# Soprano2G-010.net
KiCad netlist of a schematic drawn in EAGLE
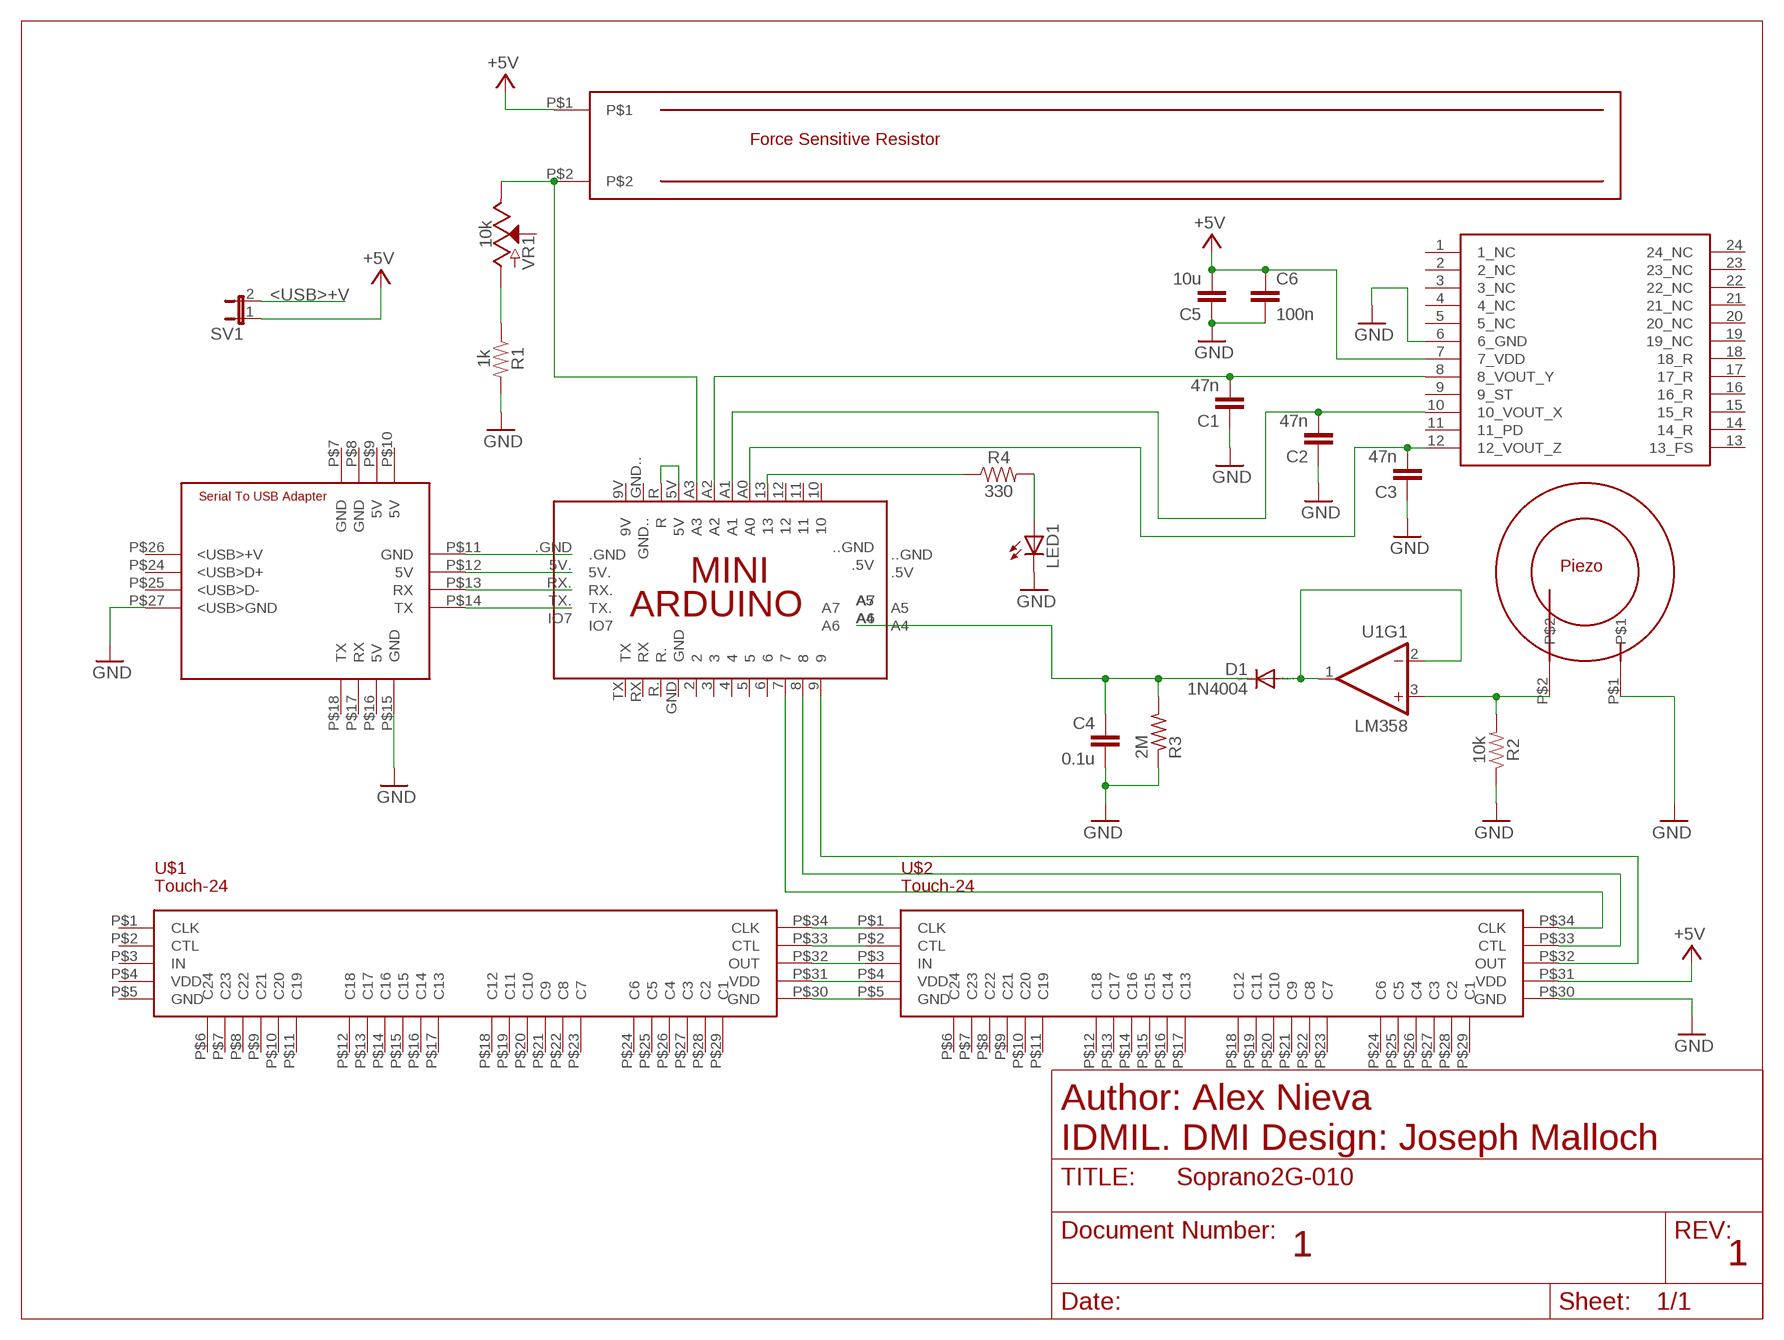
[diagram p0: schematic, sheet 1]

(export (version "E")
  (design (tool "Eeschema 10.0.6"))
  (components
    (comp (ref "C1")
      (value "47n")
      (footprint "eagle-import:C5B5.5")
      (libsource (lib "eagle-import") (part "C5/5.5"))
    )
    (comp (ref "C2")
      (value "47n")
      (footprint "eagle-import:C5B5.5")
      (libsource (lib "eagle-import") (part "C5/5.5"))
    )
    (comp (ref "C3")
      (value "47n")
      (footprint "eagle-import:C5B5.5")
      (libsource (lib "eagle-import") (part "C5/5.5"))
    )
    (comp (ref "C4")
      (value "0.1u")
      (footprint "eagle-import:C5B5.5")
      (libsource (lib "eagle-import") (part "C5/5.5"))
    )
    (comp (ref "C5")
      (value "10u")
      (footprint "eagle-import:C5B5.5")
      (libsource (lib "eagle-import") (part "C5/5.5"))
    )
    (comp (ref "C6")
      (value "100n")
      (footprint "eagle-import:C5B5.5")
      (libsource (lib "eagle-import") (part "C5/5.5"))
    )
    (comp (ref "D1")
      (value "1N4004")
      (footprint "eagle-import:DO41-10")
      (libsource (lib "eagle-import") (part "1N4004"))
    )
    (comp (ref "LED1")
      (value "LED3MM")
      (footprint "eagle-import:LED3MM")
      (libsource (lib "eagle-import") (part "LED3MM"))
    )
    (comp (ref "PCB1")
      (value "ARDUINO_MINI")
      (footprint "eagle-import:ARDUINO_MINI")
      (libsource (lib "eagle-import") (part "ARDUINO_MINI"))
    )
    (comp (ref "R1")
      (value "1k")
      (footprint "eagle-import:AXIAL-0.3")
      (libsource (lib "eagle-import") (part "1KOHM-HORIZ-1/4W-1%"))
    )
    (comp (ref "R2")
      (value "10k")
      (footprint "eagle-import:AXIAL-0.3")
      (libsource (lib "eagle-import") (part "10KOHM-HORIZ-1/4W-1%"))
    )
    (comp (ref "R3")
      (value "2M")
      (footprint "eagle-import:0204_7")
      (libsource (lib "eagle-import") (part "R-US_0204/7"))
    )
    (comp (ref "R4")
      (value "330")
      (footprint "eagle-import:AXIAL-0.3")
      (libsource (lib "eagle-import") (part "1KOHM-HORIZ-1/4W-1%"))
    )
    (comp (ref "SV1")
      (value "JP1E")
      (footprint "eagle-import:JP1")
      (libsource (lib "eagle-import") (part "JP1E"))
    )
    (comp (ref "U$1")
      (value "TOUCH-24TOUCH-24")
      (footprint "eagle-import:TOUCH24")
      (libsource (lib "eagle-import") (part "TOUCH-24TOUCH-24"))
    )
    (comp (ref "U$2")
      (value "TOUCH-24TOUCH-24")
      (footprint "eagle-import:TOUCH24")
      (libsource (lib "eagle-import") (part "TOUCH-24TOUCH-24"))
    )
    (comp (ref "U$3")
      (value "LIS3L02AS4")
      (footprint "eagle-import:SO-24")
      (libsource (lib "eagle-import") (part "LIS3L02AS4"))
    )
    (comp (ref "U$4")
      (value "SERIAL_TO_USB_ARDUINO_MINI")
      (footprint "eagle-import:SERIAL_TO_USB_ARDUINO")
      (libsource (lib "eagle-import") (part "SERIAL_TO_USB_ARDUINO_MINI"))
    )
    (comp (ref "U$5")
      (value "FSR_T-STICK")
      (footprint "eagle-import:FSR_T-STICK")
      (libsource (lib "eagle-import") (part "FSR_T-STICK"))
    )
    (comp (ref "U$6")
      (value "PIEZO_TSTICK")
      (footprint "eagle-import:PIEZO_TSTICK")
      (libsource (lib "eagle-import") (part "PIEZO_TSTICK"))
    )
    (comp (ref "U1")
      (value "LM358")
      (footprint "eagle-import:DIP08")
      (libsource (lib "eagle-import") (part "LM358"))
    )
    (comp (ref "VR1")
      (value "10k")
      (footprint "eagle-import:POT-PTH-ALPS")
      (libsource (lib "eagle-import") (part "POTENTIOMETER-PTH-9MM-1/20W-20%"))
    )
  )
  (nets
    (net (code "1") (name "+5V") (class "Default")
      (node (ref "C5") (pin "2") (pinfunction "2_2") (pintype "passive"))
      (node (ref "C6") (pin "1") (pinfunction "1_1") (pintype "passive"))
      (node (ref "PCB1") (pin "5V.") (pinfunction "5V._5V.") (pintype "bidirectional"))
      (node (ref "SV1") (pin "1") (pinfunction "1_1") (pintype "passive"))
      (node (ref "U$2") (pin "P$31") (pinfunction "VDD_P$31") (pintype "bidirectional"))
      (node (ref "U$3") (pin "7") (pinfunction "7_VDD_7") (pintype "bidirectional"))
      (node (ref "U$4") (pin "P$12") (pinfunction "5V_P$12") (pintype "bidirectional"))
      (node (ref "U$5") (pin "P$1") (pinfunction "P$1_P$1") (pintype "bidirectional"))
    )
    (net (code "2") (name "/<USB>+V") (class "Default")
      (node (ref "SV1") (pin "2") (pinfunction "2_2") (pintype "passive"))
    )
    (net (code "3") (name "GND") (class "Default")
      (node (ref "C1") (pin "1") (pinfunction "1_1") (pintype "passive"))
      (node (ref "C2") (pin "1") (pinfunction "1_1") (pintype "passive"))
      (node (ref "C3") (pin "1") (pinfunction "1_1") (pintype "passive"))
      (node (ref "C4") (pin "2") (pinfunction "2_2") (pintype "passive"))
      (node (ref "C5") (pin "1") (pinfunction "1_1") (pintype "passive"))
      (node (ref "C6") (pin "2") (pinfunction "2_2") (pintype "passive"))
      (node (ref "LED1") (pin "K") (pinfunction "C_K") (pintype "passive"))
      (node (ref "R1") (pin "P$2") (pinfunction "2_P$2") (pintype "passive"))
      (node (ref "R2") (pin "P$1") (pinfunction "1_P$1") (pintype "passive"))
      (node (ref "R3") (pin "1") (pinfunction "1_1") (pintype "passive"))
      (node (ref "U$2") (pin "P$30") (pinfunction "GND_P$30") (pintype "bidirectional"))
      (node (ref "U$3") (pin "6") (pinfunction "6_GND_6") (pintype "bidirectional"))
      (node (ref "U$4") (pin "P$15") (pinfunction "GND_P$15") (pintype "bidirectional"))
      (node (ref "U$4") (pin "P$27") (pinfunction "<USB>GND_P$27") (pintype "bidirectional"))
      (node (ref "U$6") (pin "P$1") (pinfunction "P$1_P$1") (pintype "bidirectional"))
    )
    (net (code "4") (name "Net-(C4-Pad1)") (class "Default")
      (node (ref "C4") (pin "1") (pinfunction "1_1") (pintype "passive"))
      (node (ref "D1") (pin "C") (pinfunction "C_C") (pintype "passive"))
      (node (ref "PCB1") (pin "A6") (pinfunction "A6_A6") (pintype "bidirectional"))
      (node (ref "R3") (pin "2") (pinfunction "2_2") (pintype "passive"))
    )
    (net (code "5") (name "Net-(PCB1-Pad.GND)") (class "Default")
      (node (ref "PCB1") (pin ".GND") (pinfunction ".GND_.GND") (pintype "bidirectional"))
      (node (ref "U$4") (pin "P$11") (pinfunction "GND_P$11") (pintype "bidirectional"))
    )
    (net (code "6") (name "Net-(PCB1-Pad5V)") (class "Default")
      (node (ref "PCB1") (pin "5V") (pinfunction "5V_5V") (pintype "bidirectional"))
      (node (ref "PCB1") (pin "R") (pinfunction "R_R") (pintype "bidirectional"))
    )
    (net (code "7") (name "Net-(PCB1-Pad7)") (class "Default")
      (node (ref "PCB1") (pin "7") (pinfunction "7_7") (pintype "bidirectional"))
      (node (ref "U$2") (pin "P$34") (pinfunction "CLK_P$34") (pintype "bidirectional"))
    )
    (net (code "8") (name "Net-(PCB1-Pad8)") (class "Default")
      (node (ref "PCB1") (pin "8") (pinfunction "8_8") (pintype "bidirectional"))
      (node (ref "U$2") (pin "P$33") (pinfunction "CTL_P$33") (pintype "bidirectional"))
    )
    (net (code "9") (name "Net-(PCB1-PadRX.)") (class "Default")
      (node (ref "PCB1") (pin "RX.") (pinfunction "RX._RX.") (pintype "bidirectional"))
      (node (ref "U$4") (pin "P$13") (pinfunction "RX_P$13") (pintype "bidirectional"))
    )
    (net (code "10") (name "Net-(PCB1-PadTX.)") (class "Default")
      (node (ref "PCB1") (pin "TX.") (pinfunction "TX._TX.") (pintype "bidirectional"))
      (node (ref "U$4") (pin "P$14") (pinfunction "TX_P$14") (pintype "bidirectional"))
    )
    (net (code "11") (name "Net-(R1-1)") (class "Default")
      (node (ref "R1") (pin "P$1") (pinfunction "1_P$1") (pintype "passive"))
      (node (ref "VR1") (pin "P$3") (pinfunction "A_P$3") (pintype "passive"))
    )
    (net (code "12") (name "Net-(R2-2)") (class "Default")
      (node (ref "R2") (pin "P$2") (pinfunction "2_P$2") (pintype "passive"))
      (node (ref "U$6") (pin "P$2") (pinfunction "P$2_P$2") (pintype "bidirectional"))
      (node (ref "U1") (pin "3") (pinfunction "+IN_3") (pintype "input"))
    )
    (net (code "13") (name "Net-(R4-1)") (class "Default")
      (node (ref "PCB1") (pin "13") (pinfunction "13_13") (pintype "bidirectional"))
      (node (ref "R4") (pin "P$1") (pinfunction "1_P$1") (pintype "passive"))
    )
    (net (code "14") (name "Net-(R4-2)") (class "Default")
      (node (ref "LED1") (pin "A") (pinfunction "A_A") (pintype "passive"))
      (node (ref "R4") (pin "P$2") (pinfunction "2_P$2") (pintype "passive"))
    )
    (net (code "15") (name "Net-(U$1-CLK-PadP$34)") (class "Default")
      (node (ref "U$1") (pin "P$34") (pinfunction "CLK_P$34") (pintype "bidirectional"))
      (node (ref "U$2") (pin "P$1") (pinfunction "CLK_P$1") (pintype "bidirectional"))
    )
    (net (code "16") (name "Net-(U$1-CTL-PadP$33)") (class "Default")
      (node (ref "U$1") (pin "P$33") (pinfunction "CTL_P$33") (pintype "bidirectional"))
      (node (ref "U$2") (pin "P$2") (pinfunction "CTL_P$2") (pintype "bidirectional"))
    )
    (net (code "17") (name "Net-(U$1-GND-PadP$30)") (class "Default")
      (node (ref "U$1") (pin "P$30") (pinfunction "GND_P$30") (pintype "bidirectional"))
      (node (ref "U$2") (pin "P$5") (pinfunction "GND_P$5") (pintype "bidirectional"))
    )
    (net (code "18") (name "Net-(U$1-OUT)") (class "Default")
      (node (ref "U$1") (pin "P$32") (pinfunction "OUT_P$32") (pintype "bidirectional"))
      (node (ref "U$2") (pin "P$3") (pinfunction "IN_P$3") (pintype "bidirectional"))
    )
    (net (code "19") (name "Net-(U$1-VDD-PadP$31)") (class "Default")
      (node (ref "U$1") (pin "P$31") (pinfunction "VDD_P$31") (pintype "bidirectional"))
      (node (ref "U$2") (pin "P$4") (pinfunction "VDD_P$4") (pintype "bidirectional"))
    )
    (net (code "20") (name "Net-(U$2-OUT)") (class "Default")
      (node (ref "PCB1") (pin "9") (pinfunction "9_9") (pintype "bidirectional"))
      (node (ref "U$2") (pin "P$32") (pinfunction "OUT_P$32") (pintype "bidirectional"))
    )
    (net (code "21") (name "Net-(U$3-8_VOUT_Y)") (class "Default")
      (node (ref "C1") (pin "2") (pinfunction "2_2") (pintype "passive"))
      (node (ref "PCB1") (pin "A2") (pinfunction "A2_A2") (pintype "bidirectional"))
      (node (ref "U$3") (pin "8") (pinfunction "8_VOUT_Y_8") (pintype "bidirectional"))
    )
    (net (code "22") (name "Net-(U$3-10_VOUT_X)") (class "Default")
      (node (ref "C2") (pin "2") (pinfunction "2_2") (pintype "passive"))
      (node (ref "PCB1") (pin "A1") (pinfunction "A1_A1") (pintype "bidirectional"))
      (node (ref "U$3") (pin "10") (pinfunction "10_VOUT_X_10") (pintype "bidirectional"))
    )
    (net (code "23") (name "Net-(U$3-12_VOUT_Z)") (class "Default")
      (node (ref "C3") (pin "2") (pinfunction "2_2") (pintype "passive"))
      (node (ref "PCB1") (pin "A0") (pinfunction "A0_A0") (pintype "bidirectional"))
      (node (ref "U$3") (pin "12") (pinfunction "12_VOUT_Z_12") (pintype "bidirectional"))
    )
    (net (code "24") (name "Net-(U1A--IN)") (class "Default")
      (node (ref "D1") (pin "A") (pinfunction "A_A") (pintype "passive"))
      (node (ref "U1") (pin "1") (pinfunction "OUT_1") (pintype "output"))
      (node (ref "U1") (pin "2") (pinfunction "-IN_2") (pintype "input"))
    )
    (net (code "25") (name "Net-(VR1-E)") (class "Default")
      (node (ref "PCB1") (pin "A3") (pinfunction "A3_A3") (pintype "bidirectional"))
      (node (ref "U$5") (pin "P$2") (pinfunction "P$2_P$2") (pintype "bidirectional"))
      (node (ref "VR1") (pin "P$1") (pinfunction "E_P$1") (pintype "passive"))
    )
    (net (code "26") (name "unconnected-(PCB1-Pad..GND)") (class "Default")
      (node (ref "PCB1") (pin "..GND") (pinfunction "..GND_..GND") (pintype "bidirectional"))
    )
    (net (code "27") (name "unconnected-(PCB1-Pad.5V)") (class "Default")
      (node (ref "PCB1") (pin ".5V") (pinfunction ".5V_.5V") (pintype "bidirectional"))
    )
    (net (code "28") (name "unconnected-(PCB1-Pad2)") (class "Default")
      (node (ref "PCB1") (pin "2") (pinfunction "2_2") (pintype "bidirectional"))
    )
    (net (code "29") (name "unconnected-(PCB1-Pad3)") (class "Default")
      (node (ref "PCB1") (pin "3") (pinfunction "3_3") (pintype "bidirectional"))
    )
    (net (code "30") (name "unconnected-(PCB1-Pad4)") (class "Default")
      (node (ref "PCB1") (pin "4") (pinfunction "4_4") (pintype "bidirectional"))
    )
    (net (code "31") (name "unconnected-(PCB1-Pad5)") (class "Default")
      (node (ref "PCB1") (pin "5") (pinfunction "5_5") (pintype "bidirectional"))
    )
    (net (code "32") (name "unconnected-(PCB1-Pad6)") (class "Default")
      (node (ref "PCB1") (pin "6") (pinfunction "6_6") (pintype "bidirectional"))
    )
    (net (code "33") (name "unconnected-(PCB1-Pad9V)") (class "Default")
      (node (ref "PCB1") (pin "9V") (pinfunction "9V_9V") (pintype "bidirectional"))
    )
    (net (code "34") (name "unconnected-(PCB1-Pad10)") (class "Default")
      (node (ref "PCB1") (pin "10") (pinfunction "10_10") (pintype "bidirectional"))
    )
    (net (code "35") (name "unconnected-(PCB1-Pad11)") (class "Default")
      (node (ref "PCB1") (pin "11") (pinfunction "11_11") (pintype "bidirectional"))
    )
    (net (code "36") (name "unconnected-(PCB1-Pad12)") (class "Default")
      (node (ref "PCB1") (pin "12") (pinfunction "12_12") (pintype "bidirectional"))
    )
    (net (code "37") (name "unconnected-(PCB1-PadA4)") (class "Default")
      (node (ref "PCB1") (pin "A4") (pinfunction "A4_A4") (pintype "bidirectional"))
    )
    (net (code "38") (name "unconnected-(PCB1-PadA5)") (class "Default")
      (node (ref "PCB1") (pin "A5") (pinfunction "A5_A5") (pintype "bidirectional"))
    )
    (net (code "39") (name "unconnected-(PCB1-PadA7)") (class "Default")
      (node (ref "PCB1") (pin "A7") (pinfunction "A7_A7") (pintype "bidirectional"))
    )
    (net (code "40") (name "unconnected-(PCB1-PadGND)") (class "Default")
      (node (ref "PCB1") (pin "GND") (pinfunction "GND_GND") (pintype "bidirectional"))
    )
    (net (code "41") (name "unconnected-(PCB1-PadGND..)") (class "Default")
      (node (ref "PCB1") (pin "GND..") (pinfunction "GND.._GND..") (pintype "bidirectional"))
    )
    (net (code "42") (name "unconnected-(PCB1-PadIO7)") (class "Default")
      (node (ref "PCB1") (pin "IO7") (pinfunction "IO7_IO7") (pintype "bidirectional"))
    )
    (net (code "43") (name "unconnected-(PCB1-PadR.)") (class "Default")
      (node (ref "PCB1") (pin "R.") (pinfunction "R._R.") (pintype "bidirectional"))
    )
    (net (code "44") (name "unconnected-(PCB1-PadRX)") (class "Default")
      (node (ref "PCB1") (pin "RX") (pinfunction "RX_RX") (pintype "bidirectional"))
    )
    (net (code "45") (name "unconnected-(PCB1-PadTX)") (class "Default")
      (node (ref "PCB1") (pin "TX") (pinfunction "TX_TX") (pintype "bidirectional"))
    )
    (net (code "46") (name "unconnected-(U$1-C1-PadP$29)") (class "Default")
      (node (ref "U$1") (pin "P$29") (pinfunction "C1_P$29") (pintype "bidirectional"))
    )
    (net (code "47") (name "unconnected-(U$1-C2-PadP$28)") (class "Default")
      (node (ref "U$1") (pin "P$28") (pinfunction "C2_P$28") (pintype "bidirectional"))
    )
    (net (code "48") (name "unconnected-(U$1-C3-PadP$27)") (class "Default")
      (node (ref "U$1") (pin "P$27") (pinfunction "C3_P$27") (pintype "bidirectional"))
    )
    (net (code "49") (name "unconnected-(U$1-C4-PadP$26)") (class "Default")
      (node (ref "U$1") (pin "P$26") (pinfunction "C4_P$26") (pintype "bidirectional"))
    )
    (net (code "50") (name "unconnected-(U$1-C5-PadP$25)") (class "Default")
      (node (ref "U$1") (pin "P$25") (pinfunction "C5_P$25") (pintype "bidirectional"))
    )
    (net (code "51") (name "unconnected-(U$1-C6-PadP$24)") (class "Default")
      (node (ref "U$1") (pin "P$24") (pinfunction "C6_P$24") (pintype "bidirectional"))
    )
    (net (code "52") (name "unconnected-(U$1-C7-PadP$23)") (class "Default")
      (node (ref "U$1") (pin "P$23") (pinfunction "C7_P$23") (pintype "bidirectional"))
    )
    (net (code "53") (name "unconnected-(U$1-C8-PadP$22)") (class "Default")
      (node (ref "U$1") (pin "P$22") (pinfunction "C8_P$22") (pintype "bidirectional"))
    )
    (net (code "54") (name "unconnected-(U$1-C9-PadP$21)") (class "Default")
      (node (ref "U$1") (pin "P$21") (pinfunction "C9_P$21") (pintype "bidirectional"))
    )
    (net (code "55") (name "unconnected-(U$1-C10-PadP$20)") (class "Default")
      (node (ref "U$1") (pin "P$20") (pinfunction "C10_P$20") (pintype "bidirectional"))
    )
    (net (code "56") (name "unconnected-(U$1-C11-PadP$19)") (class "Default")
      (node (ref "U$1") (pin "P$19") (pinfunction "C11_P$19") (pintype "bidirectional"))
    )
    (net (code "57") (name "unconnected-(U$1-C12-PadP$18)") (class "Default")
      (node (ref "U$1") (pin "P$18") (pinfunction "C12_P$18") (pintype "bidirectional"))
    )
    (net (code "58") (name "unconnected-(U$1-C13-PadP$17)") (class "Default")
      (node (ref "U$1") (pin "P$17") (pinfunction "C13_P$17") (pintype "bidirectional"))
    )
    (net (code "59") (name "unconnected-(U$1-C14-PadP$16)") (class "Default")
      (node (ref "U$1") (pin "P$16") (pinfunction "C14_P$16") (pintype "bidirectional"))
    )
    (net (code "60") (name "unconnected-(U$1-C15-PadP$15)") (class "Default")
      (node (ref "U$1") (pin "P$15") (pinfunction "C15_P$15") (pintype "bidirectional"))
    )
    (net (code "61") (name "unconnected-(U$1-C16-PadP$14)") (class "Default")
      (node (ref "U$1") (pin "P$14") (pinfunction "C16_P$14") (pintype "bidirectional"))
    )
    (net (code "62") (name "unconnected-(U$1-C17-PadP$13)") (class "Default")
      (node (ref "U$1") (pin "P$13") (pinfunction "C17_P$13") (pintype "bidirectional"))
    )
    (net (code "63") (name "unconnected-(U$1-C18-PadP$12)") (class "Default")
      (node (ref "U$1") (pin "P$12") (pinfunction "C18_P$12") (pintype "bidirectional"))
    )
    (net (code "64") (name "unconnected-(U$1-C19-PadP$11)") (class "Default")
      (node (ref "U$1") (pin "P$11") (pinfunction "C19_P$11") (pintype "bidirectional"))
    )
    (net (code "65") (name "unconnected-(U$1-C20-PadP$10)") (class "Default")
      (node (ref "U$1") (pin "P$10") (pinfunction "C20_P$10") (pintype "bidirectional"))
    )
    (net (code "66") (name "unconnected-(U$1-C21-PadP$9)") (class "Default")
      (node (ref "U$1") (pin "P$9") (pinfunction "C21_P$9") (pintype "bidirectional"))
    )
    (net (code "67") (name "unconnected-(U$1-C22-PadP$8)") (class "Default")
      (node (ref "U$1") (pin "P$8") (pinfunction "C22_P$8") (pintype "bidirectional"))
    )
    (net (code "68") (name "unconnected-(U$1-C23-PadP$7)") (class "Default")
      (node (ref "U$1") (pin "P$7") (pinfunction "C23_P$7") (pintype "bidirectional"))
    )
    (net (code "69") (name "unconnected-(U$1-C24-PadP$6)") (class "Default")
      (node (ref "U$1") (pin "P$6") (pinfunction "C24_P$6") (pintype "bidirectional"))
    )
    (net (code "70") (name "unconnected-(U$1-CLK-PadP$1)") (class "Default")
      (node (ref "U$1") (pin "P$1") (pinfunction "CLK_P$1") (pintype "bidirectional"))
    )
    (net (code "71") (name "unconnected-(U$1-CTL-PadP$2)") (class "Default")
      (node (ref "U$1") (pin "P$2") (pinfunction "CTL_P$2") (pintype "bidirectional"))
    )
    (net (code "72") (name "unconnected-(U$1-GND-PadP$5)") (class "Default")
      (node (ref "U$1") (pin "P$5") (pinfunction "GND_P$5") (pintype "bidirectional"))
    )
    (net (code "73") (name "unconnected-(U$1-IN-PadP$3)") (class "Default")
      (node (ref "U$1") (pin "P$3") (pinfunction "IN_P$3") (pintype "bidirectional"))
    )
    (net (code "74") (name "unconnected-(U$1-VDD-PadP$4)") (class "Default")
      (node (ref "U$1") (pin "P$4") (pinfunction "VDD_P$4") (pintype "bidirectional"))
    )
    (net (code "75") (name "unconnected-(U$2-C1-PadP$29)") (class "Default")
      (node (ref "U$2") (pin "P$29") (pinfunction "C1_P$29") (pintype "bidirectional"))
    )
    (net (code "76") (name "unconnected-(U$2-C2-PadP$28)") (class "Default")
      (node (ref "U$2") (pin "P$28") (pinfunction "C2_P$28") (pintype "bidirectional"))
    )
    (net (code "77") (name "unconnected-(U$2-C3-PadP$27)") (class "Default")
      (node (ref "U$2") (pin "P$27") (pinfunction "C3_P$27") (pintype "bidirectional"))
    )
    (net (code "78") (name "unconnected-(U$2-C4-PadP$26)") (class "Default")
      (node (ref "U$2") (pin "P$26") (pinfunction "C4_P$26") (pintype "bidirectional"))
    )
    (net (code "79") (name "unconnected-(U$2-C5-PadP$25)") (class "Default")
      (node (ref "U$2") (pin "P$25") (pinfunction "C5_P$25") (pintype "bidirectional"))
    )
    (net (code "80") (name "unconnected-(U$2-C6-PadP$24)") (class "Default")
      (node (ref "U$2") (pin "P$24") (pinfunction "C6_P$24") (pintype "bidirectional"))
    )
    (net (code "81") (name "unconnected-(U$2-C7-PadP$23)") (class "Default")
      (node (ref "U$2") (pin "P$23") (pinfunction "C7_P$23") (pintype "bidirectional"))
    )
    (net (code "82") (name "unconnected-(U$2-C8-PadP$22)") (class "Default")
      (node (ref "U$2") (pin "P$22") (pinfunction "C8_P$22") (pintype "bidirectional"))
    )
    (net (code "83") (name "unconnected-(U$2-C9-PadP$21)") (class "Default")
      (node (ref "U$2") (pin "P$21") (pinfunction "C9_P$21") (pintype "bidirectional"))
    )
    (net (code "84") (name "unconnected-(U$2-C10-PadP$20)") (class "Default")
      (node (ref "U$2") (pin "P$20") (pinfunction "C10_P$20") (pintype "bidirectional"))
    )
    (net (code "85") (name "unconnected-(U$2-C11-PadP$19)") (class "Default")
      (node (ref "U$2") (pin "P$19") (pinfunction "C11_P$19") (pintype "bidirectional"))
    )
    (net (code "86") (name "unconnected-(U$2-C12-PadP$18)") (class "Default")
      (node (ref "U$2") (pin "P$18") (pinfunction "C12_P$18") (pintype "bidirectional"))
    )
    (net (code "87") (name "unconnected-(U$2-C13-PadP$17)") (class "Default")
      (node (ref "U$2") (pin "P$17") (pinfunction "C13_P$17") (pintype "bidirectional"))
    )
    (net (code "88") (name "unconnected-(U$2-C14-PadP$16)") (class "Default")
      (node (ref "U$2") (pin "P$16") (pinfunction "C14_P$16") (pintype "bidirectional"))
    )
    (net (code "89") (name "unconnected-(U$2-C15-PadP$15)") (class "Default")
      (node (ref "U$2") (pin "P$15") (pinfunction "C15_P$15") (pintype "bidirectional"))
    )
    (net (code "90") (name "unconnected-(U$2-C16-PadP$14)") (class "Default")
      (node (ref "U$2") (pin "P$14") (pinfunction "C16_P$14") (pintype "bidirectional"))
    )
    (net (code "91") (name "unconnected-(U$2-C17-PadP$13)") (class "Default")
      (node (ref "U$2") (pin "P$13") (pinfunction "C17_P$13") (pintype "bidirectional"))
    )
    (net (code "92") (name "unconnected-(U$2-C18-PadP$12)") (class "Default")
      (node (ref "U$2") (pin "P$12") (pinfunction "C18_P$12") (pintype "bidirectional"))
    )
    (net (code "93") (name "unconnected-(U$2-C19-PadP$11)") (class "Default")
      (node (ref "U$2") (pin "P$11") (pinfunction "C19_P$11") (pintype "bidirectional"))
    )
    (net (code "94") (name "unconnected-(U$2-C20-PadP$10)") (class "Default")
      (node (ref "U$2") (pin "P$10") (pinfunction "C20_P$10") (pintype "bidirectional"))
    )
    (net (code "95") (name "unconnected-(U$2-C21-PadP$9)") (class "Default")
      (node (ref "U$2") (pin "P$9") (pinfunction "C21_P$9") (pintype "bidirectional"))
    )
    (net (code "96") (name "unconnected-(U$2-C22-PadP$8)") (class "Default")
      (node (ref "U$2") (pin "P$8") (pinfunction "C22_P$8") (pintype "bidirectional"))
    )
    (net (code "97") (name "unconnected-(U$2-C23-PadP$7)") (class "Default")
      (node (ref "U$2") (pin "P$7") (pinfunction "C23_P$7") (pintype "bidirectional"))
    )
    (net (code "98") (name "unconnected-(U$2-C24-PadP$6)") (class "Default")
      (node (ref "U$2") (pin "P$6") (pinfunction "C24_P$6") (pintype "bidirectional"))
    )
    (net (code "99") (name "unconnected-(U$3-1_NC-Pad1)") (class "Default")
      (node (ref "U$3") (pin "1") (pinfunction "1_NC_1") (pintype "bidirectional"))
    )
    (net (code "100") (name "unconnected-(U$3-2_NC-Pad2)") (class "Default")
      (node (ref "U$3") (pin "2") (pinfunction "2_NC_2") (pintype "bidirectional"))
    )
    (net (code "101") (name "unconnected-(U$3-3_NC-Pad3)") (class "Default")
      (node (ref "U$3") (pin "3") (pinfunction "3_NC_3") (pintype "bidirectional"))
    )
    (net (code "102") (name "unconnected-(U$3-4_NC-Pad4)") (class "Default")
      (node (ref "U$3") (pin "4") (pinfunction "4_NC_4") (pintype "bidirectional"))
    )
    (net (code "103") (name "unconnected-(U$3-5_NC-Pad5)") (class "Default")
      (node (ref "U$3") (pin "5") (pinfunction "5_NC_5") (pintype "bidirectional"))
    )
    (net (code "104") (name "unconnected-(U$3-9_ST-Pad9)") (class "Default")
      (node (ref "U$3") (pin "9") (pinfunction "9_ST_9") (pintype "bidirectional"))
    )
    (net (code "105") (name "unconnected-(U$3-11_PD-Pad11)") (class "Default")
      (node (ref "U$3") (pin "11") (pinfunction "11_PD_11") (pintype "bidirectional"))
    )
    (net (code "106") (name "unconnected-(U$3-13_FS-Pad13)") (class "Default")
      (node (ref "U$3") (pin "13") (pinfunction "13_FS_13") (pintype "bidirectional"))
    )
    (net (code "107") (name "unconnected-(U$3-14_R-Pad14)") (class "Default")
      (node (ref "U$3") (pin "14") (pinfunction "14_R_14") (pintype "bidirectional"))
    )
    (net (code "108") (name "unconnected-(U$3-15_R-Pad15)") (class "Default")
      (node (ref "U$3") (pin "15") (pinfunction "15_R_15") (pintype "bidirectional"))
    )
    (net (code "109") (name "unconnected-(U$3-16_R-Pad16)") (class "Default")
      (node (ref "U$3") (pin "16") (pinfunction "16_R_16") (pintype "bidirectional"))
    )
    (net (code "110") (name "unconnected-(U$3-17_R-Pad17)") (class "Default")
      (node (ref "U$3") (pin "17") (pinfunction "17_R_17") (pintype "bidirectional"))
    )
    (net (code "111") (name "unconnected-(U$3-18_R-Pad18)") (class "Default")
      (node (ref "U$3") (pin "18") (pinfunction "18_R_18") (pintype "bidirectional"))
    )
    (net (code "112") (name "unconnected-(U$3-19_NC-Pad19)") (class "Default")
      (node (ref "U$3") (pin "19") (pinfunction "19_NC_19") (pintype "bidirectional"))
    )
    (net (code "113") (name "unconnected-(U$3-20_NC-Pad20)") (class "Default")
      (node (ref "U$3") (pin "20") (pinfunction "20_NC_20") (pintype "bidirectional"))
    )
    (net (code "114") (name "unconnected-(U$3-21_NC-Pad21)") (class "Default")
      (node (ref "U$3") (pin "21") (pinfunction "21_NC_21") (pintype "bidirectional"))
    )
    (net (code "115") (name "unconnected-(U$3-22_NC-Pad22)") (class "Default")
      (node (ref "U$3") (pin "22") (pinfunction "22_NC_22") (pintype "bidirectional"))
    )
    (net (code "116") (name "unconnected-(U$3-23_NC-Pad23)") (class "Default")
      (node (ref "U$3") (pin "23") (pinfunction "23_NC_23") (pintype "bidirectional"))
    )
    (net (code "117") (name "unconnected-(U$3-24_NC-Pad24)") (class "Default")
      (node (ref "U$3") (pin "24") (pinfunction "24_NC_24") (pintype "bidirectional"))
    )
    (net (code "118") (name "unconnected-(U$4-5V-PadP$9)") (class "Default")
      (node (ref "U$4") (pin "P$9") (pinfunction "5V_P$9") (pintype "bidirectional"))
    )
    (net (code "119") (name "unconnected-(U$4-5V-PadP$10)") (class "Default")
      (node (ref "U$4") (pin "P$10") (pinfunction "5V_P$10") (pintype "bidirectional"))
    )
    (net (code "120") (name "unconnected-(U$4-5V-PadP$16)") (class "Default")
      (node (ref "U$4") (pin "P$16") (pinfunction "5V_P$16") (pintype "bidirectional"))
    )
    (net (code "121") (name "unconnected-(U$4-<USB>+V-PadP$26)") (class "Default")
      (node (ref "U$4") (pin "P$26") (pinfunction "<USB>+V_P$26") (pintype "bidirectional"))
    )
    (net (code "122") (name "unconnected-(U$4-<USB>D+-PadP$24)") (class "Default")
      (node (ref "U$4") (pin "P$24") (pinfunction "<USB>D+_P$24") (pintype "bidirectional"))
    )
    (net (code "123") (name "unconnected-(U$4-<USB>D--PadP$25)") (class "Default")
      (node (ref "U$4") (pin "P$25") (pinfunction "<USB>D-_P$25") (pintype "bidirectional"))
    )
    (net (code "124") (name "unconnected-(U$4-GND-PadP$7)") (class "Default")
      (node (ref "U$4") (pin "P$7") (pinfunction "GND_P$7") (pintype "bidirectional"))
    )
    (net (code "125") (name "unconnected-(U$4-GND-PadP$8)") (class "Default")
      (node (ref "U$4") (pin "P$8") (pinfunction "GND_P$8") (pintype "bidirectional"))
    )
    (net (code "126") (name "unconnected-(U$4-RX-PadP$17)") (class "Default")
      (node (ref "U$4") (pin "P$17") (pinfunction "RX_P$17") (pintype "bidirectional"))
    )
    (net (code "127") (name "unconnected-(U$4-TX-PadP$18)") (class "Default")
      (node (ref "U$4") (pin "P$18") (pinfunction "TX_P$18") (pintype "bidirectional"))
    )
    (net (code "128") (name "unconnected-(VR1-S-PadP$2)") (class "Default")
      (node (ref "VR1") (pin "P$2") (pinfunction "S_P$2") (pintype "passive"))
    )
  )
)
